# Triple_Axis_Accelerometer_-_Gyro_Breakou.net
KiCad netlist of a schematic drawn in EAGLE
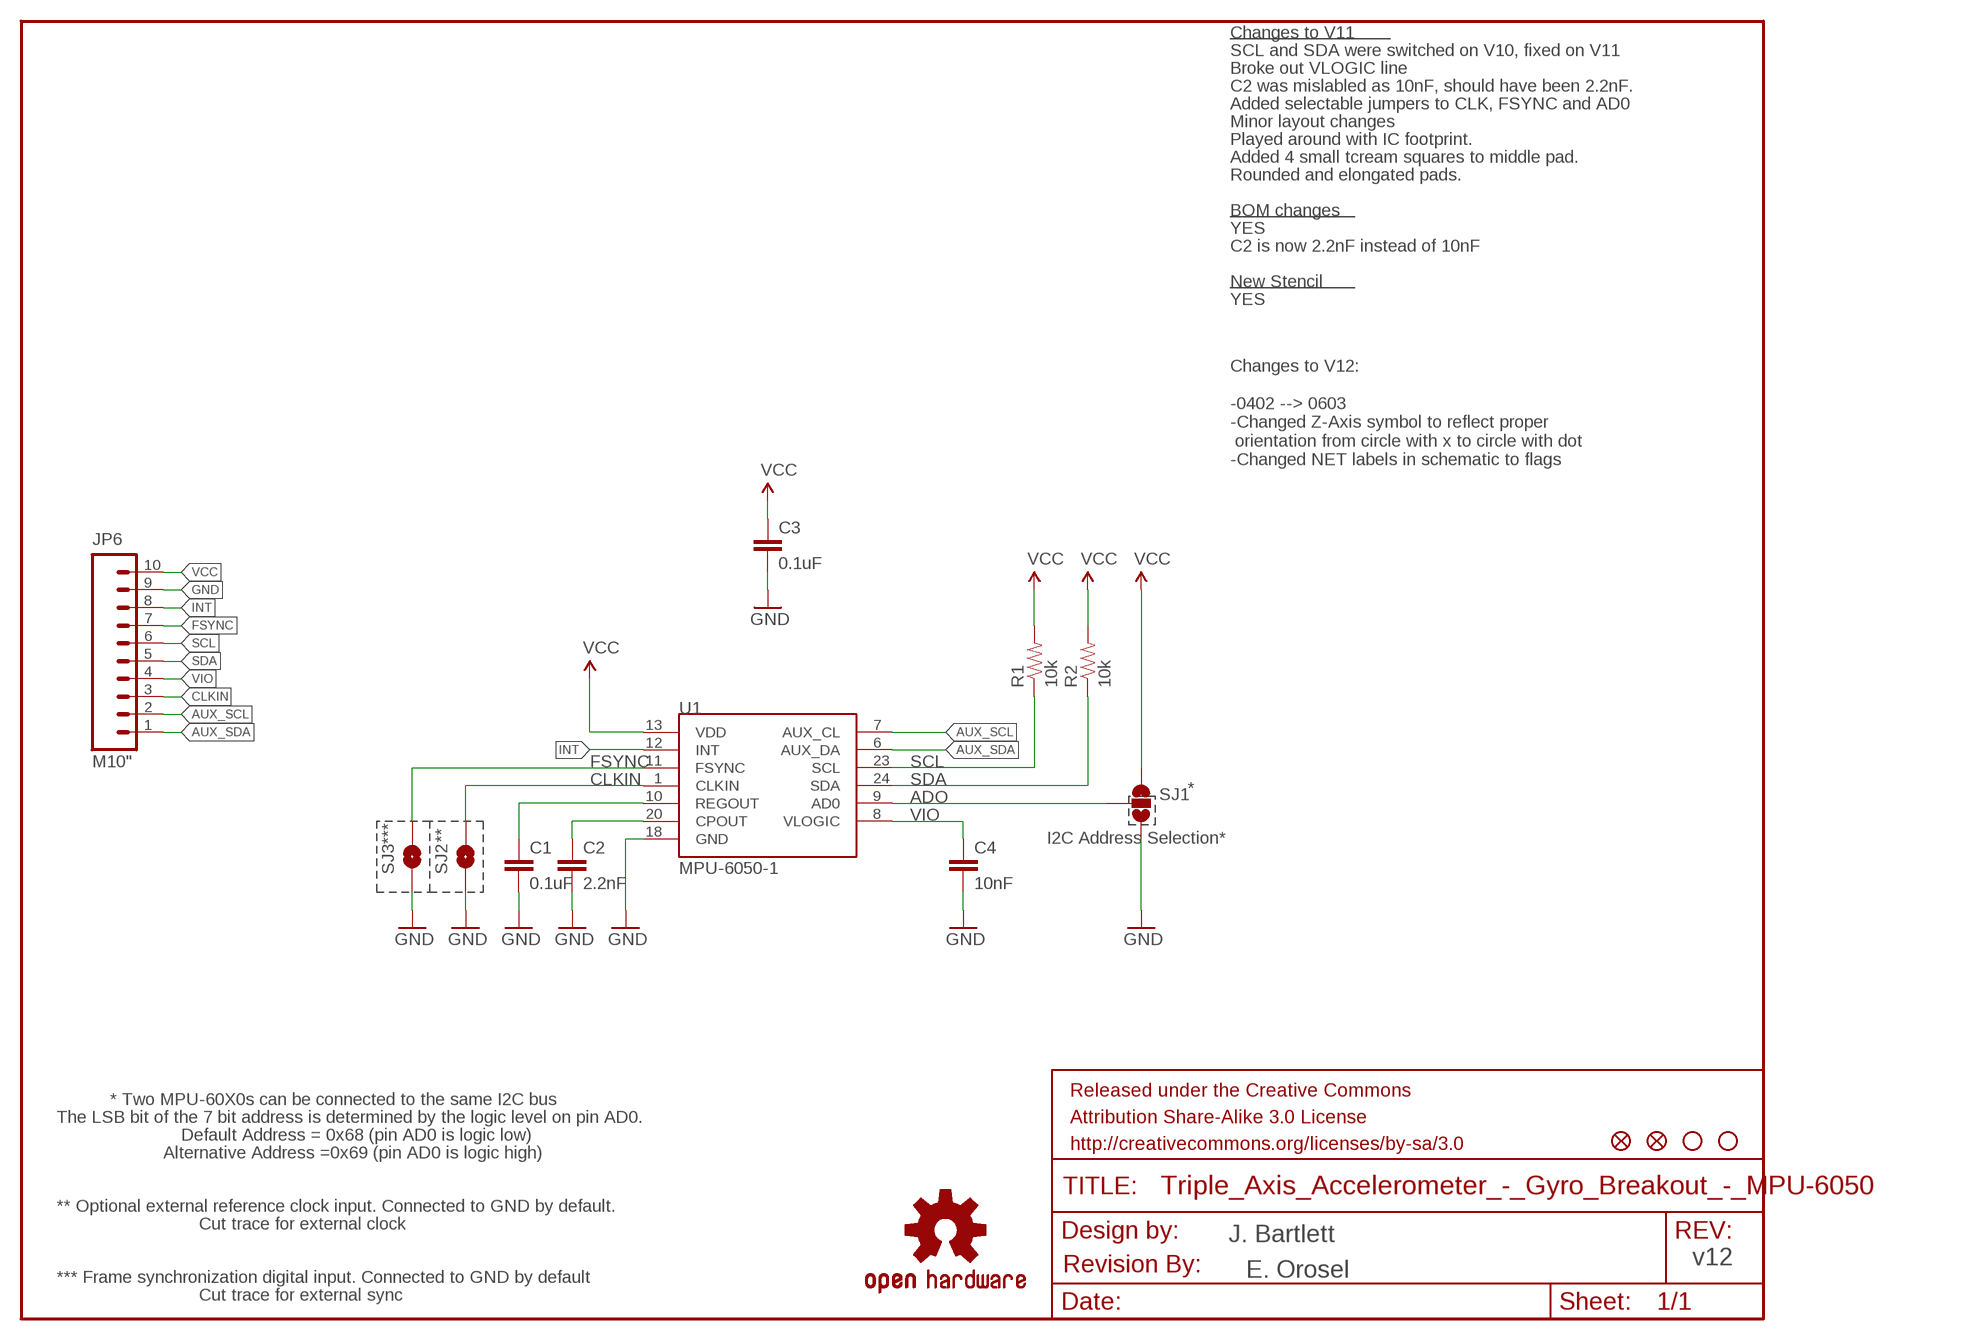
[diagram p0: schematic, sheet 1]

(export (version "E")
  (design (tool "Eeschema 10.0.6"))
  (components
    (comp (ref "C1")
      (value "0.1uF")
      (footprint "eagle-import:0603-CAP")
      (libsource (lib "eagle-import") (part "CAP0603-CAP"))
    )
    (comp (ref "C2")
      (value "2.2nF")
      (footprint "eagle-import:0603-CAP")
      (libsource (lib "eagle-import") (part "CAP0603-CAP"))
    )
    (comp (ref "C3")
      (value "0.1uF")
      (footprint "eagle-import:0603-CAP")
      (libsource (lib "eagle-import") (part "CAP0603-CAP"))
    )
    (comp (ref "C4")
      (value "10nF")
      (footprint "eagle-import:0603-CAP")
      (libsource (lib "eagle-import") (part "CAP0603-CAP"))
    )
    (comp (ref "FRAME1")
      (value "FRAME-LETTER")
      (footprint "eagle-import:CREATIVE_COMMONS")
      (libsource (lib "eagle-import") (part "FRAME-LETTER"))
    )
    (comp (ref "JP2")
      (value "FIDUCIALUFIDUCIAL")
      (footprint "eagle-import:MICRO-FIDUCIAL")
      (libsource (lib "eagle-import") (part "FIDUCIALUFIDUCIAL"))
    )
    (comp (ref "JP3")
      (value "STAND-OFFTIGHT")
      (footprint "eagle-import:STAND-OFF-TIGHT")
      (libsource (lib "eagle-import") (part "STAND-OFFTIGHT"))
    )
    (comp (ref "JP4")
      (value "STAND-OFFTIGHT")
      (footprint "eagle-import:STAND-OFF-TIGHT")
      (libsource (lib "eagle-import") (part "STAND-OFFTIGHT"))
    )
    (comp (ref "JP5")
      (value "FIDUCIALUFIDUCIAL")
      (footprint "eagle-import:MICRO-FIDUCIAL")
      (libsource (lib "eagle-import") (part "FIDUCIALUFIDUCIAL"))
    )
    (comp (ref "JP6")
      (value "M10\"")
      (footprint "eagle-import:1X10")
      (libsource (lib "eagle-import") (part "M10{dblquote}"))
    )
    (comp (ref "R1")
      (value "10k")
      (footprint "eagle-import:0603-RES")
      (libsource (lib "eagle-import") (part "RESISTOR0603-RES"))
    )
    (comp (ref "R2")
      (value "10k")
      (footprint "eagle-import:0603-RES")
      (libsource (lib "eagle-import") (part "RESISTOR0603-RES"))
    )
    (comp (ref "SJ1")
      (value "SOLDERJUMPER_2WAYPASTE2&3")
      (footprint "eagle-import:SJ_3_PASTE2&3")
      (libsource (lib "eagle-import") (part "SOLDERJUMPER_2WAYPASTE2&3"))
    )
    (comp (ref "SJ2")
      (value "SOLDERJUMPERTRACE")
      (footprint "eagle-import:SJ_2S-TRACE")
      (libsource (lib "eagle-import") (part "SOLDERJUMPERTRACE"))
    )
    (comp (ref "SJ3")
      (value "SOLDERJUMPERTRACE")
      (footprint "eagle-import:SJ_2S-TRACE")
      (libsource (lib "eagle-import") (part "SOLDERJUMPERTRACE"))
    )
    (comp (ref "U$1")
      (value "OSHW-LOGOS")
      (footprint "eagle-import:OSHW-LOGO-S")
      (libsource (lib "eagle-import") (part "OSHW-LOGOS"))
    )
    (comp (ref "U$5")
      (value "REVISION")
      (footprint "eagle-import:REVISION")
      (libsource (lib "eagle-import") (part "REVISION"))
    )
    (comp (ref "U1")
      (value "MPU-6050-1")
      (footprint "eagle-import:QFN-24-4MM2")
      (libsource (lib "eagle-import") (part "MPU-6050-1"))
    )
  )
  (nets
    (net (code "1") (name "/ADO") (class "Default")
      (node (ref "SJ1") (pin "2") (pinfunction "2_2") (pintype "passive"))
      (node (ref "U1") (pin "9") (pinfunction "AD0_9") (pintype "bidirectional"))
    )
    (net (code "2") (name "AUX_SCL") (class "Default")
      (node (ref "JP6") (pin "2") (pinfunction "2_2") (pintype "passive"))
      (node (ref "U1") (pin "7") (pinfunction "AUX_CL_7") (pintype "bidirectional"))
    )
    (net (code "3") (name "AUX_SDA") (class "Default")
      (node (ref "JP6") (pin "1") (pinfunction "1_1") (pintype "passive"))
      (node (ref "U1") (pin "6") (pinfunction "AUX_DA_6") (pintype "bidirectional"))
    )
    (net (code "4") (name "CLKIN") (class "Default")
      (node (ref "JP6") (pin "3") (pinfunction "3_3") (pintype "passive"))
      (node (ref "SJ2") (pin "2") (pinfunction "2_2") (pintype "passive"))
      (node (ref "U1") (pin "1") (pinfunction "CLKIN_1") (pintype "bidirectional"))
    )
    (net (code "5") (name "FSYNC") (class "Default")
      (node (ref "JP6") (pin "7") (pinfunction "7_7") (pintype "passive"))
      (node (ref "SJ3") (pin "2") (pinfunction "2_2") (pintype "passive"))
      (node (ref "U1") (pin "11") (pinfunction "FSYNC_11") (pintype "bidirectional"))
    )
    (net (code "6") (name "GND") (class "Default")
      (node (ref "C1") (pin "2") (pinfunction "2_2") (pintype "passive"))
      (node (ref "C2") (pin "2") (pinfunction "2_2") (pintype "passive"))
      (node (ref "C3") (pin "2") (pinfunction "2_2") (pintype "passive"))
      (node (ref "C4") (pin "2") (pinfunction "2_2") (pintype "passive"))
      (node (ref "JP6") (pin "9") (pinfunction "9_9") (pintype "passive"))
      (node (ref "SJ1") (pin "3") (pinfunction "3_3") (pintype "passive"))
      (node (ref "SJ2") (pin "1") (pinfunction "1_1") (pintype "passive"))
      (node (ref "SJ3") (pin "1") (pinfunction "1_1") (pintype "passive"))
      (node (ref "U1") (pin "18") (pinfunction "GND_18") (pintype "bidirectional"))
    )
    (net (code "7") (name "INT") (class "Default")
      (node (ref "JP6") (pin "8") (pinfunction "8_8") (pintype "passive"))
      (node (ref "U1") (pin "12") (pinfunction "INT_12") (pintype "bidirectional"))
    )
    (net (code "8") (name "Net-(U1-CPOUT)") (class "Default")
      (node (ref "C2") (pin "1") (pinfunction "1_1") (pintype "passive"))
      (node (ref "U1") (pin "20") (pinfunction "CPOUT_20") (pintype "bidirectional"))
    )
    (net (code "9") (name "Net-(U1-REGOUT)") (class "Default")
      (node (ref "C1") (pin "1") (pinfunction "1_1") (pintype "passive"))
      (node (ref "U1") (pin "10") (pinfunction "REGOUT_10") (pintype "bidirectional"))
    )
    (net (code "10") (name "SCL") (class "Default")
      (node (ref "JP6") (pin "6") (pinfunction "6_6") (pintype "passive"))
      (node (ref "R1") (pin "1") (pinfunction "1_1") (pintype "passive"))
      (node (ref "U1") (pin "23") (pinfunction "SCL_23") (pintype "bidirectional"))
    )
    (net (code "11") (name "SDA") (class "Default")
      (node (ref "JP6") (pin "5") (pinfunction "5_5") (pintype "passive"))
      (node (ref "R2") (pin "1") (pinfunction "1_1") (pintype "passive"))
      (node (ref "U1") (pin "24") (pinfunction "SDA_24") (pintype "bidirectional"))
    )
    (net (code "12") (name "VCC") (class "Default")
      (node (ref "C3") (pin "1") (pinfunction "1_1") (pintype "passive"))
      (node (ref "JP6") (pin "10") (pinfunction "10_10") (pintype "passive"))
      (node (ref "R1") (pin "2") (pinfunction "2_2") (pintype "passive"))
      (node (ref "R2") (pin "2") (pinfunction "2_2") (pintype "passive"))
      (node (ref "SJ1") (pin "1") (pinfunction "1_1") (pintype "passive"))
      (node (ref "U1") (pin "13") (pinfunction "VDD_13") (pintype "bidirectional"))
    )
    (net (code "13") (name "VIO") (class "Default")
      (node (ref "C4") (pin "1") (pinfunction "1_1") (pintype "passive"))
      (node (ref "JP6") (pin "4") (pinfunction "4_4") (pintype "passive"))
      (node (ref "U1") (pin "8") (pinfunction "VLOGIC_8") (pintype "bidirectional"))
    )
  )
)
